# AddressingMuxes_1.net
KiCad netlist of a schematic drawn in Altium Designer
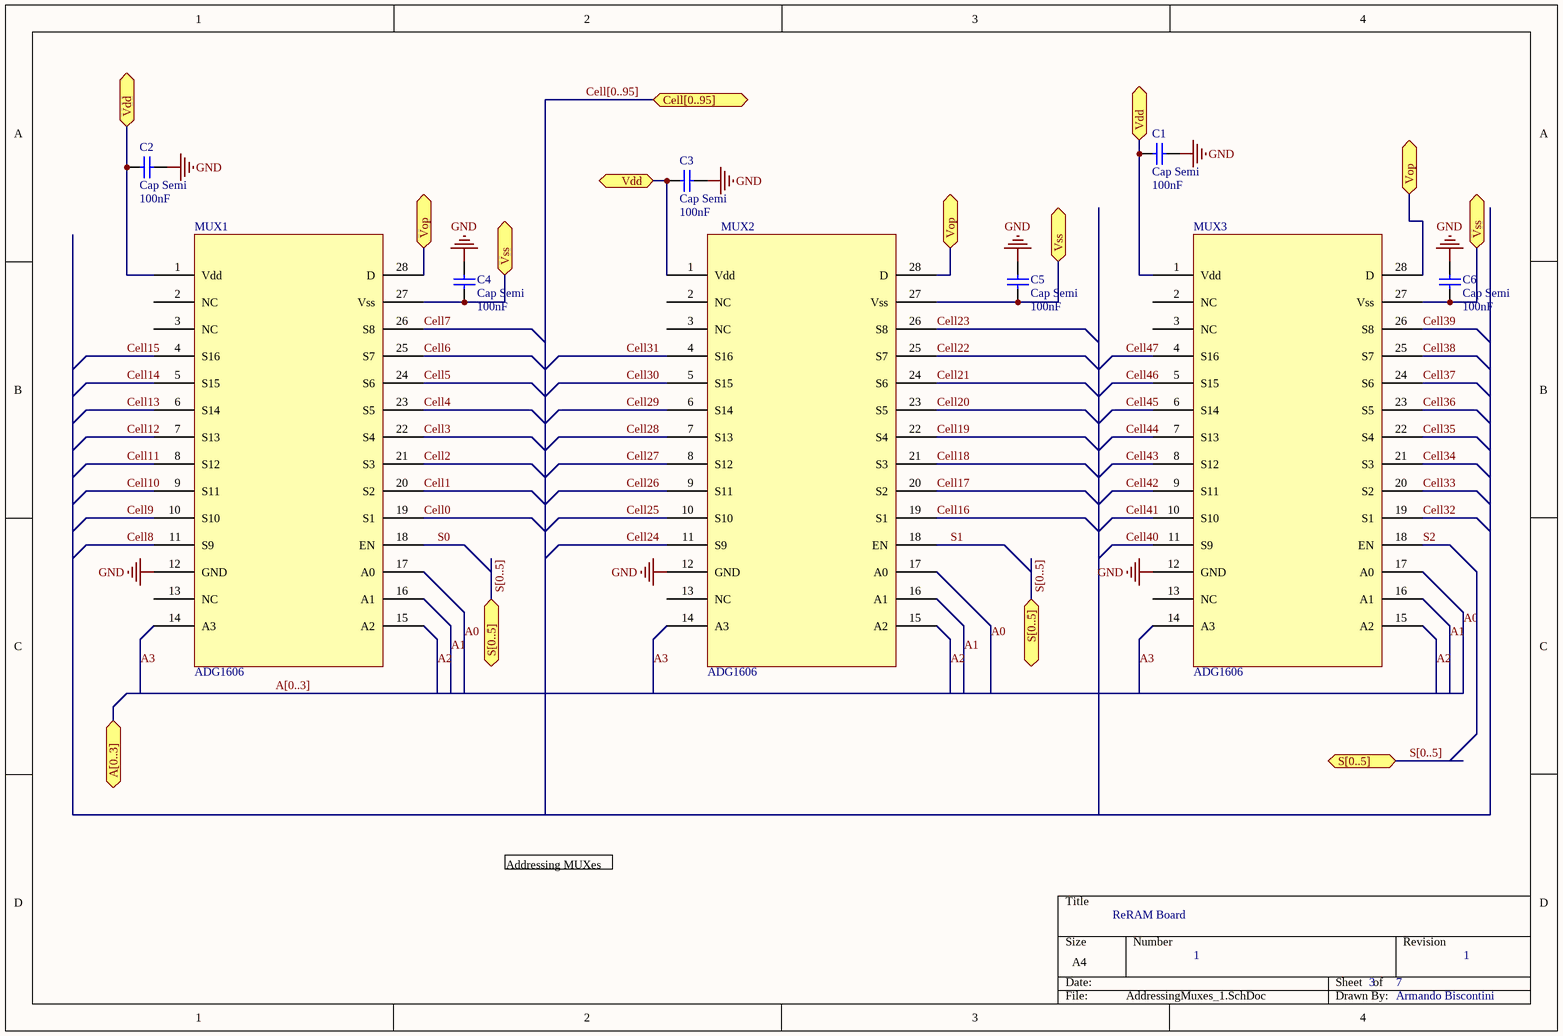
[diagram p0: AddressingMuxes_1.SchDoc]

(export (version "E")
  (design (tool "Eeschema 10.0.6"))
  (components
    (comp (ref "C1")
      (value "Cap Semi")
      (footprint "C1206")
      (description "Capacitor (Semiconductor SIM Model)")
      (fields (field (name "ALTIUM_VALUE") "100nF") (field (name "PUBLISHER") "Altium Limited"))
      (libsource (lib "Miscellaneous Devices") (part "Cap Semi"))
    )
    (comp (ref "C2")
      (value "Cap Semi")
      (footprint "C1206")
      (description "Capacitor (Semiconductor SIM Model)")
      (fields (field (name "ALTIUM_VALUE") "100nF") (field (name "PUBLISHER") "Altium Limited"))
      (libsource (lib "Miscellaneous Devices") (part "Cap Semi"))
    )
    (comp (ref "C3")
      (value "Cap Semi")
      (footprint "C1206")
      (description "Capacitor (Semiconductor SIM Model)")
      (fields (field (name "ALTIUM_VALUE") "100nF") (field (name "PUBLISHER") "Altium Limited"))
      (libsource (lib "Miscellaneous Devices") (part "Cap Semi"))
    )
    (comp (ref "C4")
      (value "Cap Semi")
      (footprint "C1206")
      (description "Capacitor (Semiconductor SIM Model)")
      (fields (field (name "ALTIUM_VALUE") "100nF") (field (name "PUBLISHER") "Altium Limited"))
      (libsource (lib "Miscellaneous Devices") (part "Cap Semi"))
    )
    (comp (ref "C5")
      (value "Cap Semi")
      (footprint "C1206")
      (description "Capacitor (Semiconductor SIM Model)")
      (fields (field (name "ALTIUM_VALUE") "100nF") (field (name "PUBLISHER") "Altium Limited"))
      (libsource (lib "Miscellaneous Devices") (part "Cap Semi"))
    )
    (comp (ref "C6")
      (value "Cap Semi")
      (footprint "C1206")
      (description "Capacitor (Semiconductor SIM Model)")
      (fields (field (name "ALTIUM_VALUE") "100nF") (field (name "PUBLISHER") "Altium Limited"))
      (libsource (lib "Miscellaneous Devices") (part "Cap Semi"))
    )
    (comp (ref "MUX1")
      (value "ADG1606")
      (footprint "TSOP65P640X120-28N")
      (description "Analog Devices ADG1606")
      (libsource (lib "ReRAM_Board_library") (part "ADG1606"))
    )
    (comp (ref "MUX2")
      (value "ADG1606")
      (footprint "TSOP65P640X120-28N")
      (description "Analog Devices ADG1606")
      (libsource (lib "ReRAM_Board_library") (part "ADG1606"))
    )
    (comp (ref "MUX3")
      (value "ADG1606")
      (footprint "TSOP65P640X120-28N")
      (description "Analog Devices ADG1606")
      (libsource (lib "ReRAM_Board_library") (part "ADG1606"))
    )
  )
  (nets
    (net (code "52") (name "/A0") (class "Default")
      (node (ref "MUX1") (pin "17") (pinfunction "A0_17") (pintype "passive"))
      (node (ref "MUX2") (pin "17") (pinfunction "A0_17") (pintype "passive"))
      (node (ref "MUX3") (pin "17") (pinfunction "A0_17") (pintype "passive"))
    )
    (net (code "53") (name "/A1") (class "Default")
      (node (ref "MUX1") (pin "16") (pinfunction "A1_16") (pintype "passive"))
      (node (ref "MUX2") (pin "16") (pinfunction "A1_16") (pintype "passive"))
      (node (ref "MUX3") (pin "16") (pinfunction "A1_16") (pintype "passive"))
    )
    (net (code "54") (name "/A2") (class "Default")
      (node (ref "MUX1") (pin "15") (pinfunction "A2_15") (pintype "passive"))
      (node (ref "MUX2") (pin "15") (pinfunction "A2_15") (pintype "passive"))
      (node (ref "MUX3") (pin "15") (pinfunction "A2_15") (pintype "passive"))
    )
    (net (code "55") (name "/A3") (class "Default")
      (node (ref "MUX1") (pin "14") (pinfunction "A3_14") (pintype "passive"))
      (node (ref "MUX2") (pin "14") (pinfunction "A3_14") (pintype "passive"))
      (node (ref "MUX3") (pin "14") (pinfunction "A3_14") (pintype "passive"))
    )
    (net (code "57") (name "/Cell0") (class "Default")
      (node (ref "MUX1") (pin "19") (pinfunction "S1_19") (pintype "passive"))
    )
    (net (code "58") (name "/Cell1") (class "Default")
      (node (ref "MUX1") (pin "20") (pinfunction "S2_20") (pintype "passive"))
    )
    (net (code "59") (name "/Cell2") (class "Default")
      (node (ref "MUX1") (pin "21") (pinfunction "S3_21") (pintype "passive"))
    )
    (net (code "60") (name "/Cell3") (class "Default")
      (node (ref "MUX1") (pin "22") (pinfunction "S4_22") (pintype "passive"))
    )
    (net (code "61") (name "/Cell4") (class "Default")
      (node (ref "MUX1") (pin "23") (pinfunction "S5_23") (pintype "passive"))
    )
    (net (code "62") (name "/Cell5") (class "Default")
      (node (ref "MUX1") (pin "24") (pinfunction "S6_24") (pintype "passive"))
    )
    (net (code "63") (name "/Cell6") (class "Default")
      (node (ref "MUX1") (pin "25") (pinfunction "S7_25") (pintype "passive"))
    )
    (net (code "64") (name "/Cell7") (class "Default")
      (node (ref "MUX1") (pin "26") (pinfunction "S8_26") (pintype "passive"))
    )
    (net (code "65") (name "/Cell8") (class "Default")
      (node (ref "MUX1") (pin "11") (pinfunction "S9_11") (pintype "passive"))
    )
    (net (code "66") (name "/Cell9") (class "Default")
      (node (ref "MUX1") (pin "10") (pinfunction "S10_10") (pintype "passive"))
    )
    (net (code "67") (name "/Cell10") (class "Default")
      (node (ref "MUX1") (pin "9") (pinfunction "S11_9") (pintype "passive"))
    )
    (net (code "68") (name "/Cell11") (class "Default")
      (node (ref "MUX1") (pin "8") (pinfunction "S12_8") (pintype "passive"))
    )
    (net (code "69") (name "/Cell12") (class "Default")
      (node (ref "MUX1") (pin "7") (pinfunction "S13_7") (pintype "passive"))
    )
    (net (code "70") (name "/Cell13") (class "Default")
      (node (ref "MUX1") (pin "6") (pinfunction "S14_6") (pintype "passive"))
    )
    (net (code "71") (name "/Cell14") (class "Default")
      (node (ref "MUX1") (pin "5") (pinfunction "S15_5") (pintype "passive"))
    )
    (net (code "72") (name "/Cell15") (class "Default")
      (node (ref "MUX1") (pin "4") (pinfunction "S16_4") (pintype "passive"))
    )
    (net (code "73") (name "/Cell16") (class "Default")
      (node (ref "MUX2") (pin "19") (pinfunction "S1_19") (pintype "passive"))
    )
    (net (code "74") (name "/Cell17") (class "Default")
      (node (ref "MUX2") (pin "20") (pinfunction "S2_20") (pintype "passive"))
    )
    (net (code "75") (name "/Cell18") (class "Default")
      (node (ref "MUX2") (pin "21") (pinfunction "S3_21") (pintype "passive"))
    )
    (net (code "76") (name "/Cell19") (class "Default")
      (node (ref "MUX2") (pin "22") (pinfunction "S4_22") (pintype "passive"))
    )
    (net (code "77") (name "/Cell20") (class "Default")
      (node (ref "MUX2") (pin "23") (pinfunction "S5_23") (pintype "passive"))
    )
    (net (code "78") (name "/Cell21") (class "Default")
      (node (ref "MUX2") (pin "24") (pinfunction "S6_24") (pintype "passive"))
    )
    (net (code "79") (name "/Cell22") (class "Default")
      (node (ref "MUX2") (pin "25") (pinfunction "S7_25") (pintype "passive"))
    )
    (net (code "80") (name "/Cell23") (class "Default")
      (node (ref "MUX2") (pin "26") (pinfunction "S8_26") (pintype "passive"))
    )
    (net (code "81") (name "/Cell24") (class "Default")
      (node (ref "MUX2") (pin "11") (pinfunction "S9_11") (pintype "passive"))
    )
    (net (code "82") (name "/Cell25") (class "Default")
      (node (ref "MUX2") (pin "10") (pinfunction "S10_10") (pintype "passive"))
    )
    (net (code "83") (name "/Cell26") (class "Default")
      (node (ref "MUX2") (pin "9") (pinfunction "S11_9") (pintype "passive"))
    )
    (net (code "84") (name "/Cell27") (class "Default")
      (node (ref "MUX2") (pin "8") (pinfunction "S12_8") (pintype "passive"))
    )
    (net (code "85") (name "/Cell28") (class "Default")
      (node (ref "MUX2") (pin "7") (pinfunction "S13_7") (pintype "passive"))
    )
    (net (code "86") (name "/Cell29") (class "Default")
      (node (ref "MUX2") (pin "6") (pinfunction "S14_6") (pintype "passive"))
    )
    (net (code "87") (name "/Cell30") (class "Default")
      (node (ref "MUX2") (pin "5") (pinfunction "S15_5") (pintype "passive"))
    )
    (net (code "88") (name "/Cell31") (class "Default")
      (node (ref "MUX2") (pin "4") (pinfunction "S16_4") (pintype "passive"))
    )
    (net (code "89") (name "/Cell32") (class "Default")
      (node (ref "MUX3") (pin "19") (pinfunction "S1_19") (pintype "passive"))
    )
    (net (code "90") (name "/Cell33") (class "Default")
      (node (ref "MUX3") (pin "20") (pinfunction "S2_20") (pintype "passive"))
    )
    (net (code "91") (name "/Cell34") (class "Default")
      (node (ref "MUX3") (pin "21") (pinfunction "S3_21") (pintype "passive"))
    )
    (net (code "92") (name "/Cell35") (class "Default")
      (node (ref "MUX3") (pin "22") (pinfunction "S4_22") (pintype "passive"))
    )
    (net (code "93") (name "/Cell36") (class "Default")
      (node (ref "MUX3") (pin "23") (pinfunction "S5_23") (pintype "passive"))
    )
    (net (code "94") (name "/Cell37") (class "Default")
      (node (ref "MUX3") (pin "24") (pinfunction "S6_24") (pintype "passive"))
    )
    (net (code "95") (name "/Cell38") (class "Default")
      (node (ref "MUX3") (pin "25") (pinfunction "S7_25") (pintype "passive"))
    )
    (net (code "96") (name "/Cell39") (class "Default")
      (node (ref "MUX3") (pin "26") (pinfunction "S8_26") (pintype "passive"))
    )
    (net (code "97") (name "/Cell40") (class "Default")
      (node (ref "MUX3") (pin "11") (pinfunction "S9_11") (pintype "passive"))
    )
    (net (code "98") (name "/Cell41") (class "Default")
      (node (ref "MUX3") (pin "10") (pinfunction "S10_10") (pintype "passive"))
    )
    (net (code "99") (name "/Cell42") (class "Default")
      (node (ref "MUX3") (pin "9") (pinfunction "S11_9") (pintype "passive"))
    )
    (net (code "100") (name "/Cell43") (class "Default")
      (node (ref "MUX3") (pin "8") (pinfunction "S12_8") (pintype "passive"))
    )
    (net (code "101") (name "/Cell44") (class "Default")
      (node (ref "MUX3") (pin "7") (pinfunction "S13_7") (pintype "passive"))
    )
    (net (code "102") (name "/Cell45") (class "Default")
      (node (ref "MUX3") (pin "6") (pinfunction "S14_6") (pintype "passive"))
    )
    (net (code "103") (name "/Cell46") (class "Default")
      (node (ref "MUX3") (pin "5") (pinfunction "S15_5") (pintype "passive"))
    )
    (net (code "104") (name "/Cell47") (class "Default")
      (node (ref "MUX3") (pin "4") (pinfunction "S16_4") (pintype "passive"))
    )
    (net (code "106") (name "/S0") (class "Default")
      (node (ref "MUX1") (pin "18") (pinfunction "EN_18") (pintype "passive"))
    )
    (net (code "107") (name "/S1") (class "Default")
      (node (ref "MUX2") (pin "18") (pinfunction "EN_18") (pintype "passive"))
    )
    (net (code "108") (name "/S2") (class "Default")
      (node (ref "MUX3") (pin "18") (pinfunction "EN_18") (pintype "passive"))
    )
    (net (code "110") (name "/Vdd") (class "Default")
      (node (ref "C1") (pin "2") (pinfunction "2_2") (pintype "passive"))
      (node (ref "C2") (pin "1") (pinfunction "1_1") (pintype "passive"))
      (node (ref "C3") (pin "1") (pinfunction "1_1") (pintype "passive"))
      (node (ref "MUX1") (pin "1") (pinfunction "Vdd_1") (pintype "passive"))
      (node (ref "MUX2") (pin "1") (pinfunction "Vdd_1") (pintype "passive"))
      (node (ref "MUX3") (pin "1") (pinfunction "Vdd_1") (pintype "passive"))
    )
    (net (code "111") (name "/Vop") (class "Default")
      (node (ref "MUX1") (pin "28") (pinfunction "D_28") (pintype "passive"))
      (node (ref "MUX2") (pin "28") (pinfunction "D_28") (pintype "passive"))
      (node (ref "MUX3") (pin "28") (pinfunction "D_28") (pintype "passive"))
    )
    (net (code "112") (name "/Vss") (class "Default")
      (node (ref "C4") (pin "1") (pinfunction "1_1") (pintype "passive"))
      (node (ref "C5") (pin "1") (pinfunction "1_1") (pintype "passive"))
      (node (ref "C6") (pin "2") (pinfunction "2_2") (pintype "passive"))
      (node (ref "MUX1") (pin "27") (pinfunction "Vss_27") (pintype "passive"))
      (node (ref "MUX2") (pin "27") (pinfunction "Vss_27") (pintype "passive"))
      (node (ref "MUX3") (pin "27") (pinfunction "Vss_27") (pintype "passive"))
    )
    (net (code "113") (name "GND") (class "Default")
      (node (ref "C1") (pin "1") (pinfunction "1_1") (pintype "passive"))
      (node (ref "C2") (pin "2") (pinfunction "2_2") (pintype "passive"))
      (node (ref "C3") (pin "2") (pinfunction "2_2") (pintype "passive"))
      (node (ref "C4") (pin "2") (pinfunction "2_2") (pintype "passive"))
      (node (ref "C5") (pin "2") (pinfunction "2_2") (pintype "passive"))
      (node (ref "C6") (pin "1") (pinfunction "1_1") (pintype "passive"))
      (node (ref "MUX1") (pin "12") (pinfunction "GND_12") (pintype "passive"))
      (node (ref "MUX2") (pin "12") (pinfunction "GND_12") (pintype "passive"))
      (node (ref "MUX3") (pin "12") (pinfunction "GND_12") (pintype "passive"))
    )
    (net (code "114") (name "unconnected-(MUX1-NC-Pad2)") (class "Default")
      (node (ref "MUX1") (pin "2") (pinfunction "NC_2") (pintype "passive"))
    )
    (net (code "115") (name "unconnected-(MUX1-NC-Pad3)") (class "Default")
      (node (ref "MUX1") (pin "3") (pinfunction "NC_3") (pintype "passive"))
    )
    (net (code "116") (name "unconnected-(MUX1-NC-Pad13)") (class "Default")
      (node (ref "MUX1") (pin "13") (pinfunction "NC_13") (pintype "passive"))
    )
    (net (code "117") (name "unconnected-(MUX2-NC-Pad2)") (class "Default")
      (node (ref "MUX2") (pin "2") (pinfunction "NC_2") (pintype "passive"))
    )
    (net (code "118") (name "unconnected-(MUX2-NC-Pad3)") (class "Default")
      (node (ref "MUX2") (pin "3") (pinfunction "NC_3") (pintype "passive"))
    )
    (net (code "119") (name "unconnected-(MUX2-NC-Pad13)") (class "Default")
      (node (ref "MUX2") (pin "13") (pinfunction "NC_13") (pintype "passive"))
    )
    (net (code "120") (name "unconnected-(MUX3-NC-Pad2)") (class "Default")
      (node (ref "MUX3") (pin "2") (pinfunction "NC_2") (pintype "passive"))
    )
    (net (code "121") (name "unconnected-(MUX3-NC-Pad3)") (class "Default")
      (node (ref "MUX3") (pin "3") (pinfunction "NC_3") (pintype "passive"))
    )
    (net (code "122") (name "unconnected-(MUX3-NC-Pad13)") (class "Default")
      (node (ref "MUX3") (pin "13") (pinfunction "NC_13") (pintype "passive"))
    )
  )
)
